# 2022_AESK_UAV_Power.net
KiCad netlist of a schematic drawn in Altium Designer
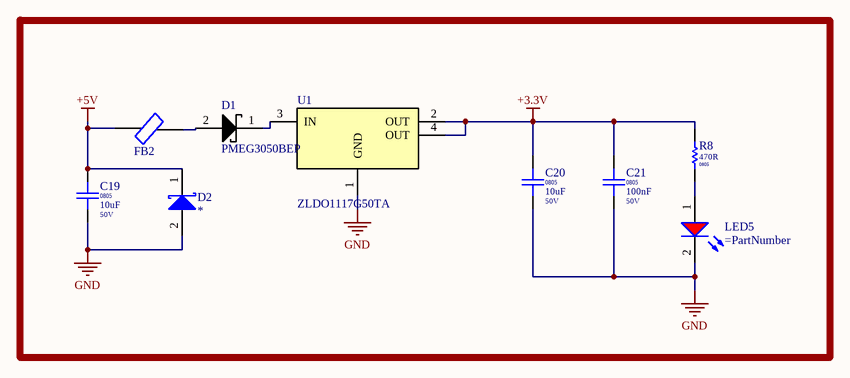
[diagram p0: 2022_AESK_UAV_Power.SchDoc]

(export (version "E")
  (design (tool "Eeschema 10.0.6"))
  (components
    (comp (ref "C19")
      (value "10uF")
      (footprint "CAPC 0805")
      (description "Capacitor Ceramic 10uF 50V 0805")
      (fields
        (field (name "PACKAGE / CASE") "0805")
        (field (name "VOLTAGE") "50V")
        (field (name "PART NUMBER") "CAPC0588")
      )
      (libsource (lib "Aesk Database Library") (part "NPCapacitor"))
    )
    (comp (ref "C20")
      (value "10uF")
      (footprint "CAPC 0805")
      (description "Capacitor Ceramic 10uF 50V 0805")
      (fields
        (field (name "PACKAGE / CASE") "0805")
        (field (name "VOLTAGE") "50V")
        (field (name "PART NUMBER") "CAPC0588")
      )
      (libsource (lib "Aesk Database Library") (part "NPCapacitor"))
    )
    (comp (ref "C21")
      (value "100nF")
      (footprint "CAPC 0805")
      (description "Capacitor Ceramic 100nF 50V 0805")
      (fields
        (field (name "PACKAGE / CASE") "0805")
        (field (name "VOLTAGE") "50V")
        (field (name "PART NUMBER") "CAPC0572")
      )
      (libsource (lib "Aesk Database Library") (part "NPCapacitor"))
    )
    (comp (ref "D1")
      (value "PMEG3050BEP")
      (footprint "SOD470X100-2N")
      (description "Schotky Diode")
      (fields
        (field (name "MANUFACTURER") "Nexperia USA")
        (field (name "MANUFACTURER PART NUMBER") "PMEG3050BEP,115")
      )
      (libsource (lib "2022_AESK_UAV") (part "Schotky Diode"))
    )
    (comp (ref "D2")
      (value "*")
      (footprint "DO-214AC, SMA")
      (fields (field (name "PART NUMBER") "Diode0012"))
      (libsource (lib "AESK Database Library") (part "Schottky Diode"))
    )
    (comp (ref "FB2")
      (value "Ferrite Bead")
      (footprint "FCM1608KF-601T03")
      (libsource (lib "2022_AESK_UAV") (part "FCM1608KF-601T03"))
    )
    (comp (ref "LED5")
      (value "~")
      (footprint "LED RED 0805")
      (description "LED")
      (libsource (lib "Diodes_GESK") (part "LED RED"))
    )
    (comp (ref "R8")
      (value "470R")
      (footprint "RESC 0805")
      (description "470R 0805")
      (fields (field (name "PACKAGE / CASE") "0805") (field (name "PART NUMBER") "R0334"))
      (libsource (lib "Aesk Database Library") (part "Resistor"))
    )
    (comp (ref "U1")
      (value "ZLDO1117G50TA")
      (footprint "1117")
      (description "IC REG LDO 5V 1A SOT223")
      (libsource (lib "UAV_UcusKontrolKartı_Sematik_Kutuphane") (part "ZLDO1117G50TA"))
    )
  )
  (nets
    (net (code "1") (name "+3.3V") (class "Default")
      (node (ref "C20") (pin "2") (pinfunction "2_2") (pintype "passive"))
      (node (ref "C21") (pin "2") (pinfunction "2_2") (pintype "passive"))
      (node (ref "R8") (pin "2") (pinfunction "2_2") (pintype "passive"))
      (node (ref "U1") (pin "2") (pinfunction "OUT_2") (pintype "power_in"))
      (node (ref "U1") (pin "4") (pinfunction "OUT_4") (pintype "power_in"))
    )
    (net (code "2") (name "+5V") (class "Default")
      (node (ref "C19") (pin "2") (pinfunction "2_2") (pintype "passive"))
      (node (ref "D2") (pin "1") (pinfunction "K_1") (pintype "passive"))
      (node (ref "FB2") (pin "2") (pinfunction "2_2") (pintype "passive"))
    )
    (net (code "3") (name "GND") (class "Default")
      (node (ref "C19") (pin "1") (pinfunction "1_1") (pintype "passive"))
      (node (ref "C20") (pin "1") (pinfunction "1_1") (pintype "passive"))
      (node (ref "C21") (pin "1") (pinfunction "1_1") (pintype "passive"))
      (node (ref "D2") (pin "2") (pinfunction "A_2") (pintype "passive"))
      (node (ref "LED5") (pin "2") (pinfunction "C_2") (pintype "passive"))
      (node (ref "U1") (pin "1") (pinfunction "GND_1") (pintype "power_in"))
    )
    (net (code "4") (name "Net-(D1-A)") (class "Default")
      (node (ref "D1") (pin "2") (pinfunction "A_2") (pintype "passive"))
      (node (ref "FB2") (pin "1") (pinfunction "1_1") (pintype "passive"))
    )
    (net (code "5") (name "Net-(D1-K)") (class "Default")
      (node (ref "D1") (pin "1") (pinfunction "K_1") (pintype "passive"))
      (node (ref "U1") (pin "3") (pinfunction "IN_3") (pintype "power_in"))
    )
    (net (code "6") (name "Net-(LED5-A)") (class "Default")
      (node (ref "LED5") (pin "1") (pinfunction "A_1") (pintype "passive"))
      (node (ref "R8") (pin "1") (pinfunction "1_1") (pintype "passive"))
    )
  )
)
